# busanalizer.net
KiCad netlist of a schematic drawn in Altium Designer
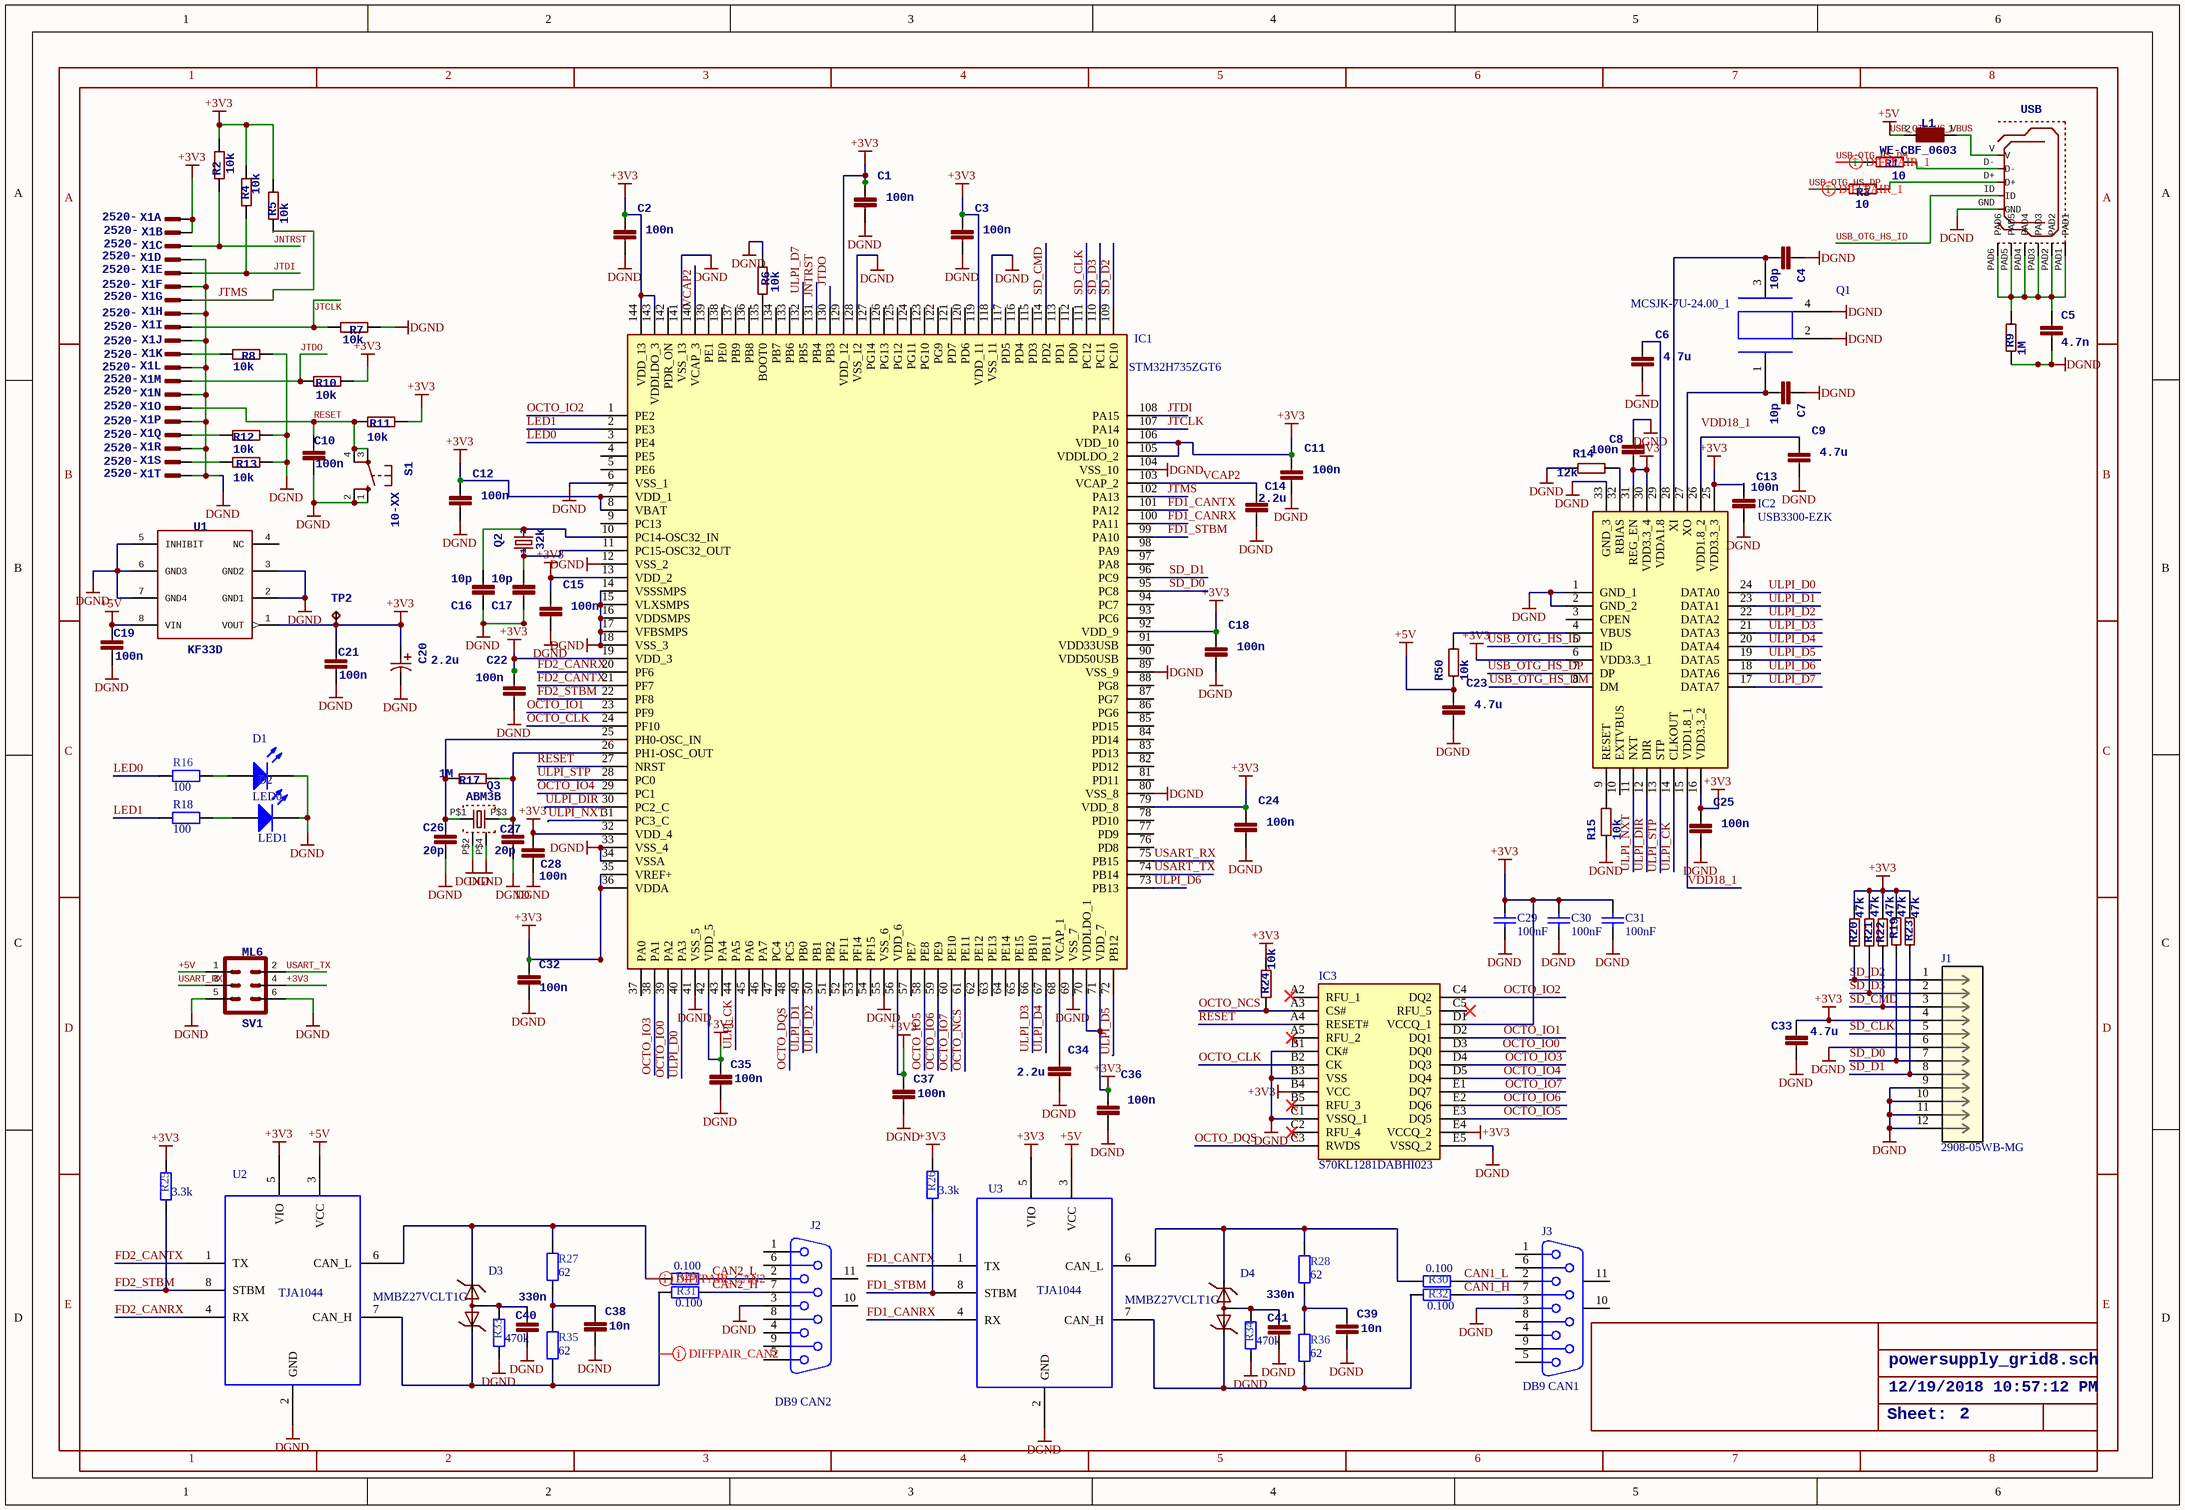
[diagram p0: busanalizer.SchDoc]

(export (version "E")
  (design (tool "Eeschema 10.0.6"))
  (components
    (comp (ref "C1")
      (value "100n")
      (footprint "C0402")
      (description "<B>CAPACITOR</B>, European symbol")
      (libsource (lib "rcl") (part "C-EUC0402"))
    )
    (comp (ref "C2")
      (value "100n")
      (footprint "C0402")
      (description "<B>CAPACITOR</B>, European symbol")
      (libsource (lib "rcl") (part "C-EUC0402"))
    )
    (comp (ref "C3")
      (value "100n")
      (footprint "C0402")
      (description "<B>CAPACITOR</B>, European symbol")
      (libsource (lib "rcl") (part "C-EUC0402"))
    )
    (comp (ref "C4")
      (value "10p")
      (footprint "C0402")
      (description "<B>CAPACITOR</B>, European symbol")
      (libsource (lib "") (part "C-EUC0402_2"))
    )
    (comp (ref "C5")
      (value "4.7n")
      (footprint "C0805")
      (description "<B>CAPACITOR</B>, European symbol")
      (libsource (lib "rcl") (part "C-EUC0805"))
    )
    (comp (ref "C6")
      (value "4.7u")
      (footprint "rcl:C0805")
      (description "<B>CAPACITOR</B>, European symbol")
      (libsource (lib "rcl") (part "C-EUC0402"))
    )
    (comp (ref "C7")
      (value "10p")
      (footprint "C0402")
      (description "<B>CAPACITOR</B>, European symbol")
      (libsource (lib "") (part "C-EUC0402_2"))
    )
    (comp (ref "C8")
      (value "100n")
      (footprint "C0402")
      (description "<B>CAPACITOR</B>, European symbol")
      (libsource (lib "") (part "C-EUC0402_1"))
    )
    (comp (ref "C9")
      (value "4.7u")
      (footprint "rcl:C0805")
      (description "<B>CAPACITOR</B>, European symbol")
      (libsource (lib "rcl") (part "C-EUC0402"))
    )
    (comp (ref "C10")
      (value "100n")
      (footprint "C0402")
      (description "<B>CAPACITOR</B>, European symbol")
      (libsource (lib "rcl") (part "C-EUC0402"))
    )
    (comp (ref "C11")
      (value "100n")
      (footprint "C0402")
      (description "<B>CAPACITOR</B>, European symbol")
      (libsource (lib "rcl") (part "C-EUC0402"))
    )
    (comp (ref "C12")
      (value "100n")
      (footprint "C0402")
      (description "<B>CAPACITOR</B>, European symbol")
      (libsource (lib "rcl") (part "C-EUC0402"))
    )
    (comp (ref "C13")
      (value "100n")
      (footprint "C0402")
      (description "<B>CAPACITOR</B>, European symbol")
      (libsource (lib "rcl") (part "C-EUC0402"))
    )
    (comp (ref "C14")
      (value "2.2u")
      (footprint "rcl:C0805")
      (description "<B>CAPACITOR</B>, European symbol")
      (libsource (lib "rcl") (part "C-EUC0402"))
    )
    (comp (ref "C15")
      (value "100n")
      (footprint "C0402")
      (description "<B>CAPACITOR</B>, European symbol")
      (libsource (lib "rcl") (part "C-EUC0402"))
    )
    (comp (ref "C16")
      (value "10p")
      (footprint "C0402")
      (description "<B>CAPACITOR</B>, European symbol")
      (libsource (lib "") (part "C-EUC0402_1"))
    )
    (comp (ref "C17")
      (value "10p")
      (footprint "C0402")
      (description "<B>CAPACITOR</B>, European symbol")
      (libsource (lib "") (part "C-EUC0402_1"))
    )
    (comp (ref "C18")
      (value "100n")
      (footprint "C0402")
      (description "<B>CAPACITOR</B>, European symbol")
      (libsource (lib "rcl") (part "C-EUC0402"))
    )
    (comp (ref "C19")
      (value "100n")
      (footprint "C0603")
      (description "<B>CAPACITOR</B>, European symbol")
      (libsource (lib "rcl") (part "C-EUC0603"))
    )
    (comp (ref "C20")
      (value "2.2u")
      (footprint "Panasonic-EEEFT_EEEH:CAPAE430X610N")
      (fields
        (field (name "MPN") "EEE-FT0J101AR")
        (field (name "TOLERANCE") "±20 %")
        (field (name "MPN_1") "EEE-FT1A680AR")
      )
      (libsource (lib "Panasonic-EEEFT_EEEH") (part "EEE--CASE-B"))
    )
    (comp (ref "C21")
      (value "100n")
      (footprint "C0603")
      (description "<B>CAPACITOR</B>, European symbol")
      (libsource (lib "rcl") (part "C-EUC0603"))
    )
    (comp (ref "C22")
      (value "100n")
      (footprint "C0402")
      (description "<B>CAPACITOR</B>, European symbol")
      (libsource (lib "rcl") (part "C-EUC0402"))
    )
    (comp (ref "C23")
      (value "4.7u")
      (footprint "rcl:C0805")
      (description "<B>CAPACITOR</B>, European symbol")
      (libsource (lib "rcl") (part "C-EUC0402"))
    )
    (comp (ref "C24")
      (value "100n")
      (footprint "C0402")
      (description "<B>CAPACITOR</B>, European symbol")
      (libsource (lib "rcl") (part "C-EUC0402"))
    )
    (comp (ref "C25")
      (value "100n")
      (footprint "C0402")
      (description "<B>CAPACITOR</B>, European symbol")
      (libsource (lib "rcl") (part "C-EUC0402"))
    )
    (comp (ref "C26")
      (value "20p")
      (footprint "C0402")
      (description "<B>CAPACITOR</B>, European symbol")
      (libsource (lib "rcl") (part "C-EUC0402"))
    )
    (comp (ref "C27")
      (value "20p")
      (footprint "C0402")
      (description "<B>CAPACITOR</B>, European symbol")
      (libsource (lib "rcl") (part "C-EUC0402"))
    )
    (comp (ref "C28")
      (value "100n")
      (footprint "C0402")
      (description "<B>CAPACITOR</B>, European symbol")
      (libsource (lib "rcl") (part "C-EUC0402"))
    )
    (comp (ref "C29")
      (value "100nF")
      (footprint "C0402")
      (description "Capacitor, MLCC, 100nF, 16V, X7R, 10%, 0402, T=0,5mm")
      (fields
        (field (name "INTERNAL_PART_NUMBER") "MCD-00102")
        (field (name "MANUFACTURER_PART_NUMBER") "CC0402KRX7R7BB104")
        (field (name "PROVIDED_BY") "SUBCO")
      )
      (libsource (lib "MCD_PARTS_database") (part "Capacitor"))
    )
    (comp (ref "C30")
      (value "100nF")
      (footprint "C0402")
      (description "Capacitor, MLCC, 100nF, 16V, X7R, 10%, 0402, T=0,5mm")
      (fields
        (field (name "INTERNAL_PART_NUMBER") "MCD-00102")
        (field (name "MANUFACTURER_PART_NUMBER") "CC0402KRX7R7BB104")
        (field (name "PROVIDED_BY") "SUBCO")
      )
      (libsource (lib "MCD_PARTS_database") (part "Capacitor"))
    )
    (comp (ref "C31")
      (value "100nF")
      (footprint "C0402")
      (description "Capacitor, MLCC, 100nF, 16V, X7R, 10%, 0402, T=0,5mm")
      (fields
        (field (name "INTERNAL_PART_NUMBER") "MCD-00102")
        (field (name "MANUFACTURER_PART_NUMBER") "CC0402KRX7R7BB104")
        (field (name "PROVIDED_BY") "SUBCO")
      )
      (libsource (lib "MCD_PARTS_database") (part "Capacitor"))
    )
    (comp (ref "C32")
      (value "100n")
      (footprint "C0402")
      (description "<B>CAPACITOR</B>, European symbol")
      (libsource (lib "rcl") (part "C-EUC0402"))
    )
    (comp (ref "C33")
      (value "4.7u")
      (footprint "rcl:C0805")
      (description "<B>CAPACITOR</B>, European symbol")
      (libsource (lib "rcl") (part "C-EUC0402"))
    )
    (comp (ref "C34")
      (value "2.2u")
      (footprint "rcl:C0805")
      (description "<B>CAPACITOR</B>, European symbol")
      (libsource (lib "rcl") (part "C-EUC0402"))
    )
    (comp (ref "C35")
      (value "100n")
      (footprint "C0402")
      (description "<B>CAPACITOR</B>, European symbol")
      (libsource (lib "rcl") (part "C-EUC0402"))
    )
    (comp (ref "C36")
      (value "100n")
      (footprint "C0402")
      (description "<B>CAPACITOR</B>, European symbol")
      (libsource (lib "rcl") (part "C-EUC0402"))
    )
    (comp (ref "C37")
      (value "100n")
      (footprint "C0402")
      (description "<B>CAPACITOR</B>, European symbol")
      (libsource (lib "rcl") (part "C-EUC0402"))
    )
    (comp (ref "C38")
      (value "10n")
      (footprint "C0805")
      (description "<B>CAPACITOR</B>, European symbol")
      (libsource (lib "rcl") (part "C-EUC0402"))
    )
    (comp (ref "C39")
      (value "10n")
      (footprint "C0805")
      (description "<B>CAPACITOR</B>, European symbol")
      (libsource (lib "rcl") (part "C-EUC0402"))
    )
    (comp (ref "C40")
      (value "330n")
      (footprint "C0805")
      (description "<B>CAPACITOR</B>, European symbol")
      (libsource (lib "rcl") (part "C-EUC0402"))
    )
    (comp (ref "C41")
      (value "330n")
      (footprint "C0805")
      (description "<B>CAPACITOR</B>, European symbol")
      (libsource (lib "rcl") (part "C-EUC0402"))
    )
    (comp (ref "D1")
      (value "LED0")
      (footprint "LED-0")
      (description "Typical INFRARED GaAs LED")
      (fields (field (name "PUBLISHER") "Altium Limited"))
      (libsource (lib "Miscellaneous Devices") (part "LED0"))
    )
    (comp (ref "D2")
      (value "LED1")
      (footprint "LED-0")
      (description "Typical INFRARED GaAs LED")
      (fields (field (name "PUBLISHER") "Altium Limited"))
      (libsource (lib "Miscellaneous Devices") (part "LED0"))
    )
    (comp (ref "D3")
      (value "MMBZ27VCLT1G")
      (footprint "SOT23")
      (libsource (lib "MMBZ27VCLT1G") (part "MMBZ27VCLT1G"))
    )
    (comp (ref "D4")
      (value "MMBZ27VCLT1G")
      (footprint "SOT23")
      (libsource (lib "MMBZ27VCLT1G") (part "MMBZ27VCLT1G"))
    )
    (comp (ref "IC1")
      (value "STM32H735ZGT6")
      (footprint "SamacSys:QFP50P2200X2200X160-144N")
      (description "Integrated Circuit")
      (libsource (lib "*") (part "STM32H735ZGT6"))
    )
    (comp (ref "IC2")
      (value "USB3300-EZK")
      (footprint "SamacSys:QFN50P500X500X100-33N-D")
      (description "Integrated Circuit")
      (fields (field (name "MOUSER2 PART NUMBER") "886-USB3300-EZK"))
      (libsource (lib "*") (part "USB3300-EZK"))
    )
    (comp (ref "IC3")
      (value "S70KL1281DABHI023")
      (footprint "SamacSys:BGA24C100P5X5_600X800X100")
      (description "Integrated Circuit")
      (libsource (lib "*") (part "S70KL1281DABHI023"))
    )
    (comp (ref "J1")
      (value "2908-05WB-MG")
      (footprint "CONN_3M_2900")
      (description "No Description Available")
      (fields (field (name "COPYRIGHT") "Copyright (C) 2018 Accelerated Designs. All rights reserved"))
      (libsource (lib "2021-01-25_15-19-21") (part "2908-05WB-MG"))
    )
    (comp (ref "J2")
      (value "DB9 CAN2")
      (footprint "DSUB1.385-2H9")
      (description "Receptacle Assembly, 9 Position, Right Angle")
      (fields (field (name "PUBLISHER") "Altium Limited"))
      (libsource (lib "Miscellaneous Connectors") (part "D Connector 9"))
    )
    (comp (ref "J3")
      (value "DB9 CAN1")
      (footprint "DSUB1.385-2H9")
      (description "Receptacle Assembly, 9 Position, Right Angle")
      (fields (field (name "PUBLISHER") "Altium Limited"))
      (libsource (lib "Miscellaneous Connectors") (part "D Connector 9"))
    )
    (comp (ref "L1")
      (value "WE-CBF_0603")
      (footprint "WE-CBF:0603")
      (fields (field (name "MPN") "742792695"))
      (libsource (lib "WE-CBF") (part "WE-CBF_0603"))
    )
    (comp (ref "Q1")
      (value "MCSJK-7U-24.00_1")
      (footprint "MCSJK-7U-24.00_1")
      (libsource (lib "MCSJK-7U-24.00") (part "MCSJK-7U-24.00_1"))
    )
    (comp (ref "Q2")
      (value "32k")
      (footprint "crystal:TC26V")
      (description "<b>CRYSTAL</b>")
      (fields (field (name "1") "1") (field (name "2") "2"))
      (libsource (lib "crystal") (part "CRYSTALTC26V"))
    )
    (comp (ref "Q3")
      (value "ABM3B")
      (footprint "crystal_my:ABM3B")
      (libsource (lib "crystal_my") (part "ABM3B"))
    )
    (comp (ref "R1")
      (value "10")
      (footprint "R0805")
      (description "<B>RESISTOR</B>, European symbol")
      (libsource (lib "rcl") (part "R-EU_R0805"))
    )
    (comp (ref "R2")
      (value "10k")
      (footprint "R0805")
      (description "<B>RESISTOR</B>, European symbol")
      (libsource (lib "rcl") (part "R-EU_R0805"))
    )
    (comp (ref "R3")
      (value "10")
      (footprint "R0805")
      (description "<B>RESISTOR</B>, European symbol")
      (libsource (lib "rcl") (part "R-EU_R0805"))
    )
    (comp (ref "R4")
      (value "10k")
      (footprint "R0805")
      (description "<B>RESISTOR</B>, European symbol")
      (libsource (lib "rcl") (part "R-EU_R0805"))
    )
    (comp (ref "R5")
      (value "10k")
      (footprint "R0805")
      (description "<B>RESISTOR</B>, European symbol")
      (libsource (lib "rcl") (part "R-EU_R0805"))
    )
    (comp (ref "R6")
      (value "10k")
      (footprint "R0805")
      (description "<B>RESISTOR</B>, European symbol")
      (libsource (lib "rcl") (part "R-EU_R0805"))
    )
    (comp (ref "R7")
      (value "10k")
      (footprint "R0805")
      (description "<B>RESISTOR</B>, European symbol")
      (libsource (lib "rcl") (part "R-EU_R0805"))
    )
    (comp (ref "R8")
      (value "10k")
      (footprint "R0805")
      (description "<B>RESISTOR</B>, European symbol")
      (libsource (lib "rcl") (part "R-EU_R0805"))
    )
    (comp (ref "R9")
      (value "1M")
      (footprint "R0805")
      (description "<B>RESISTOR</B>, European symbol")
      (libsource (lib "rcl") (part "R-EU_R0805"))
    )
    (comp (ref "R10")
      (value "10k")
      (footprint "R0805")
      (description "<B>RESISTOR</B>, European symbol")
      (libsource (lib "rcl") (part "R-EU_R0805"))
    )
    (comp (ref "R11")
      (value "10k")
      (footprint "R0805")
      (description "<B>RESISTOR</B>, European symbol")
      (libsource (lib "rcl") (part "R-EU_R0805"))
    )
    (comp (ref "R12")
      (value "10k")
      (footprint "R0805")
      (description "<B>RESISTOR</B>, European symbol")
      (libsource (lib "rcl") (part "R-EU_R0805"))
    )
    (comp (ref "R13")
      (value "10k")
      (footprint "R0805")
      (description "<B>RESISTOR</B>, European symbol")
      (libsource (lib "rcl") (part "R-EU_R0805"))
    )
    (comp (ref "R14") (value "12k") (footprint "R0805") (libsource (lib "rcl") (part "R-EU_R0805")))
    (comp (ref "R15") (value "10k") (footprint "R0805") (libsource (lib "rcl") (part "R-EU_R0805")))
    (comp (ref "R16")
      (value "100")
      (footprint "6-0805_L")
      (description "Resistor")
      (fields (field (name "Comment") "Res2") (field (name "PUBLISHER") "Altium Limited"))
      (libsource (lib "Miscellaneous Devices") (part "Res2"))
    )
    (comp (ref "R17")
      (value "1M")
      (footprint "R0402")
      (description "<B>RESISTOR</B>, European symbol")
      (libsource (lib "rcl") (part "R-EU_R0402"))
    )
    (comp (ref "R18")
      (value "100")
      (footprint "6-0805_L")
      (description "Resistor")
      (fields (field (name "Comment") "Res2") (field (name "PUBLISHER") "Altium Limited"))
      (libsource (lib "Miscellaneous Devices") (part "Res2"))
    )
    (comp (ref "R19")
      (value "47k")
      (footprint "R0805")
      (description "<B>RESISTOR</B>, European symbol")
      (libsource (lib "rcl") (part "R-EU_R0805"))
    )
    (comp (ref "R20")
      (value "47k")
      (footprint "R0805")
      (description "<B>RESISTOR</B>, European symbol")
      (libsource (lib "rcl") (part "R-EU_R0805"))
    )
    (comp (ref "R21")
      (value "47k")
      (footprint "R0805")
      (description "<B>RESISTOR</B>, European symbol")
      (libsource (lib "rcl") (part "R-EU_R0805"))
    )
    (comp (ref "R22")
      (value "47k")
      (footprint "R0805")
      (description "<B>RESISTOR</B>, European symbol")
      (libsource (lib "rcl") (part "R-EU_R0805"))
    )
    (comp (ref "R23")
      (value "47k")
      (footprint "R0805")
      (description "<B>RESISTOR</B>, European symbol")
      (libsource (lib "rcl") (part "R-EU_R0805"))
    )
    (comp (ref "R24")
      (value "10k")
      (footprint "R0805")
      (description "<B>RESISTOR</B>, European symbol")
      (libsource (lib "rcl") (part "R-EU_R0805"))
    )
    (comp (ref "R25")
      (value "3.3k")
      (footprint "R0805")
      (description "Resistor")
      (fields (field (name "Comment") "Res2") (field (name "PUBLISHER") "Altium Limited"))
      (libsource (lib "") (part "Res2_1"))
    )
    (comp (ref "R26")
      (value "3.3k")
      (footprint "R0805")
      (description "Resistor")
      (fields (field (name "Comment") "Res2") (field (name "PUBLISHER") "Altium Limited"))
      (libsource (lib "") (part "Res2_1"))
    )
    (comp (ref "R27")
      (value "62")
      (footprint "R0805")
      (description "Resistor")
      (fields (field (name "Comment") "Res2") (field (name "PUBLISHER") "Altium Limited"))
      (libsource (lib "") (part "Res2_1"))
    )
    (comp (ref "R28")
      (value "62")
      (footprint "R0805")
      (description "Resistor")
      (fields (field (name "Comment") "Res2") (field (name "PUBLISHER") "Altium Limited"))
      (libsource (lib "") (part "Res2_1"))
    )
    (comp (ref "R29")
      (value "0.100")
      (footprint "R0805")
      (description "Resistor")
      (fields (field (name "Comment") "Res2") (field (name "PUBLISHER") "Altium Limited"))
      (libsource (lib "Miscellaneous Devices") (part "Res2"))
    )
    (comp (ref "R30")
      (value "0.100")
      (footprint "R0805")
      (description "Resistor")
      (fields (field (name "Comment") "Res2") (field (name "PUBLISHER") "Altium Limited"))
      (libsource (lib "Miscellaneous Devices") (part "Res2"))
    )
    (comp (ref "R31")
      (value "0.100")
      (footprint "R0805")
      (description "Resistor")
      (fields (field (name "Comment") "Res2") (field (name "PUBLISHER") "Altium Limited"))
      (libsource (lib "Miscellaneous Devices") (part "Res2"))
    )
    (comp (ref "R32")
      (value "0.100")
      (footprint "R0805")
      (description "Resistor")
      (fields (field (name "Comment") "Res2") (field (name "PUBLISHER") "Altium Limited"))
      (libsource (lib "Miscellaneous Devices") (part "Res2"))
    )
    (comp (ref "R33")
      (value "470k")
      (footprint "R0805")
      (description "Resistor")
      (fields (field (name "Comment") "Res2") (field (name "PUBLISHER") "Altium Limited"))
      (libsource (lib "") (part "Res2_1"))
    )
    (comp (ref "R34")
      (value "470k")
      (footprint "R0805")
      (description "Resistor")
      (fields (field (name "Comment") "Res2") (field (name "PUBLISHER") "Altium Limited"))
      (libsource (lib "") (part "Res2_1"))
    )
    (comp (ref "R35")
      (value "62")
      (footprint "R0805")
      (description "Resistor")
      (fields (field (name "Comment") "Res2") (field (name "PUBLISHER") "Altium Limited"))
      (libsource (lib "") (part "Res2_1"))
    )
    (comp (ref "R36")
      (value "62")
      (footprint "R0805")
      (description "Resistor")
      (fields (field (name "Comment") "Res2") (field (name "PUBLISHER") "Altium Limited"))
      (libsource (lib "") (part "Res2_1"))
    )
    (comp (ref "R50") (value "10k") (footprint "R0805") (libsource (lib "rcl") (part "R-EU_R0805")))
    (comp (ref "S1")
      (value "10-XX")
      (footprint "switch-omron:B3F-10XX")
      (description "<b>OMRON SWITCH</b>")
      (fields (field (name "MPN") "B3F-1000"))
      (libsource (lib "switch-omron") (part "10-XX"))
    )
    (comp (ref "SV1")
      (value "ML6")
      (footprint "con-harting-ml:ML6")
      (description "<b>HARTING</b>")
      (libsource (lib "con-harting-ml") (part "ML6"))
    )
    (comp (ref "TP2")
      (value "TPB2,54")
      (footprint "B2,54")
      (description "<b>Test pad</b>")
      (libsource (lib "testpad") (part "TPB2,54"))
    )
    (comp (ref "U1") (value "KF33D") (footprint "KF33BD:SO8") (libsource (lib "KF33BD") (part "KF33D")))
    (comp (ref "U2") (value "TJA1044") (footprint "SO8") (libsource (lib "TJA1044") (part "TJA1044")))
    (comp (ref "U3") (value "TJA1044") (footprint "SO8") (libsource (lib "TJA1044") (part "TJA1044")))
    (comp (ref "USB1")
      (value "USB_MICROB")
      (footprint "usb_hinrose:USB_MICROB_PACKAGE")
      (description "This is the hirose ZX62-B-5PA(11) MICRO-USB B Type female connection.")
      (fields (field (name "USB") "USB"))
      (libsource (lib "usb_hinrose") (part "USB_MICROB"))
    )
    (comp (ref "X1")
      (value "2520-")
      (footprint "con-3m:PAK100/2500-20")
      (description "<b>3M (TM) Pak 100 4-Wall Header</b><p>\nSource: 3M")
      (libsource (lib "con-3m") (part "2520-"))
    )
  )
  (nets
    (net (code "1") (name "+3V3") (class "Default")
      (node (ref "C1") (pin "1") (pinfunction "1_1") (pintype "passive"))
      (node (ref "C11") (pin "1") (pinfunction "1_1") (pintype "passive"))
      (node (ref "C12") (pin "1") (pinfunction "1_1") (pintype "passive"))
      (node (ref "C13") (pin "1") (pinfunction "1_1") (pintype "passive"))
      (node (ref "C15") (pin "1") (pinfunction "1_1") (pintype "passive"))
      (node (ref "C18") (pin "1") (pinfunction "1_1") (pintype "passive"))
      (node (ref "C2") (pin "1") (pinfunction "1_1") (pintype "passive"))
      (node (ref "C20") (pin "1") (pinfunction "1_1") (pintype "passive"))
      (node (ref "C21") (pin "1") (pinfunction "1_1") (pintype "passive"))
      (node (ref "C22") (pin "1") (pinfunction "1_1") (pintype "passive"))
      (node (ref "C24") (pin "1") (pinfunction "1_1") (pintype "passive"))
      (node (ref "C25") (pin "1") (pinfunction "1_1") (pintype "passive"))
      (node (ref "C28") (pin "1") (pinfunction "1_1") (pintype "passive"))
      (node (ref "C29") (pin "2") (pinfunction "2_2") (pintype "passive"))
      (node (ref "C3") (pin "1") (pinfunction "1_1") (pintype "passive"))
      (node (ref "C30") (pin "2") (pinfunction "2_2") (pintype "passive"))
      (node (ref "C31") (pin "2") (pinfunction "2_2") (pintype "passive"))
      (node (ref "C32") (pin "1") (pinfunction "1_1") (pintype "passive"))
      (node (ref "C33") (pin "1") (pinfunction "1_1") (pintype "passive"))
      (node (ref "C35") (pin "1") (pinfunction "1_1") (pintype "passive"))
      (node (ref "C36") (pin "1") (pinfunction "1_1") (pintype "passive"))
      (node (ref "C37") (pin "1") (pinfunction "1_1") (pintype "passive"))
      (node (ref "C8") (pin "1") (pinfunction "1_1") (pintype "passive"))
      (node (ref "IC1") (pin "105") (pinfunction "VDDLDO_2_105") (pintype "passive"))
      (node (ref "IC1") (pin "106") (pinfunction "VDD_10_106") (pintype "passive"))
      (node (ref "IC1") (pin "119") (pinfunction "VDD_11_119") (pintype "passive"))
      (node (ref "IC1") (pin "129") (pinfunction "VDD_12_129") (pintype "passive"))
      (node (ref "IC1") (pin "13") (pinfunction "VDD_2_13") (pintype "passive"))
      (node (ref "IC1") (pin "143") (pinfunction "VDDLDO_3_143") (pintype "passive"))
      (node (ref "IC1") (pin "144") (pinfunction "VDD_13_144") (pintype "passive"))
      (node (ref "IC1") (pin "19") (pinfunction "VDD_3_19") (pintype "passive"))
      (node (ref "IC1") (pin "32") (pinfunction "VDD_4_32") (pintype "passive"))
      (node (ref "IC1") (pin "35") (pinfunction "VREF+_35") (pintype "passive"))
      (node (ref "IC1") (pin "36") (pinfunction "VDDA_36") (pintype "passive"))
      (node (ref "IC1") (pin "42") (pinfunction "VDD_5_42") (pintype "passive"))
      (node (ref "IC1") (pin "56") (pinfunction "VDD_6_56") (pintype "passive"))
      (node (ref "IC1") (pin "7") (pinfunction "VDD_1_7") (pintype "passive"))
      (node (ref "IC1") (pin "70") (pinfunction "VDDLDO_1_70") (pintype "passive"))
      (node (ref "IC1") (pin "71") (pinfunction "VDD_7_71") (pintype "passive"))
      (node (ref "IC1") (pin "79") (pinfunction "VDD_8_79") (pintype "passive"))
      (node (ref "IC1") (pin "8") (pinfunction "VBAT_8") (pintype "passive"))
      (node (ref "IC1") (pin "92") (pinfunction "VDD_9_92") (pintype "passive"))
      (node (ref "IC2") (pin "16") (pinfunction "VDD3.3_2_16") (pintype "passive"))
      (node (ref "IC2") (pin "25") (pinfunction "VDD3.3_3_25") (pintype "passive"))
      (node (ref "IC2") (pin "30") (pinfunction "VDD3.3_4_30") (pintype "passive"))
      (node (ref "IC2") (pin "31") (pinfunction "REG_EN_31") (pintype "passive"))
      (node (ref "IC2") (pin "6") (pinfunction "VDD3.3_1_6") (pintype "passive"))
      (node (ref "IC3") (pin "B4") (pinfunction "VCC_B4") (pintype "passive"))
      (node (ref "IC3") (pin "D1") (pinfunction "VCCQ_1_D1") (pintype "passive"))
      (node (ref "IC3") (pin "E4") (pinfunction "VCCQ_2_E4") (pintype "passive"))
      (node (ref "J1") (pin "4") (pinfunction "4_4") (pintype "passive"))
      (node (ref "R10") (pin "1") (pinfunction "1_1") (pintype "passive"))
      (node (ref "R11") (pin "1") (pinfunction "1_1") (pintype "passive"))
      (node (ref "R19") (pin "2") (pinfunction "2_2") (pintype "passive"))
      (node (ref "R2") (pin "2") (pinfunction "2_2") (pintype "passive"))
      (node (ref "R20") (pin "2") (pinfunction "2_2") (pintype "passive"))
      (node (ref "R21") (pin "2") (pinfunction "2_2") (pintype "passive"))
      (node (ref "R22") (pin "2") (pinfunction "2_2") (pintype "passive"))
      (node (ref "R23") (pin "2") (pinfunction "2_2") (pintype "passive"))
      (node (ref "R24") (pin "2") (pinfunction "2_2") (pintype "passive"))
      (node (ref "R25") (pin "2") (pinfunction "2_2") (pintype "passive"))
      (node (ref "R26") (pin "2") (pinfunction "2_2") (pintype "passive"))
      (node (ref "R4") (pin "2") (pinfunction "2_2") (pintype "passive"))
      (node (ref "R5") (pin "2") (pinfunction "2_2") (pintype "passive"))
      (node (ref "SV1") (pin "4") (pinfunction "4_4") (pintype "passive"))
      (node (ref "TP2") (pin "TP") (pinfunction "TP_TP") (pintype "passive"))
      (node (ref "U1") (pin "1") (pinfunction "VOUT_1") (pintype "output"))
      (node (ref "U2") (pin "5") (pinfunction "VIO_5") (pintype "passive"))
      (node (ref "U3") (pin "5") (pinfunction "VIO_5") (pintype "passive"))
      (node (ref "X1") (pin "1") (pinfunction "KL_1") (pintype "passive"))
      (node (ref "X1") (pin "2") (pinfunction "KL_2") (pintype "passive"))
    )
    (net (code "2") (name "+5V") (class "Default")
      (node (ref "C19") (pin "1") (pinfunction "1_1") (pintype "passive"))
      (node (ref "C23") (pin "1") (pinfunction "1_1") (pintype "passive"))
      (node (ref "L1") (pin "2") (pinfunction "2_2") (pintype "passive"))
      (node (ref "R50") (pin "1") (pinfunction "1_1") (pintype "passive"))
      (node (ref "SV1") (pin "1") (pinfunction "1_1") (pintype "passive"))
      (node (ref "U1") (pin "8") (pinfunction "VIN_8") (pintype "passive"))
      (node (ref "U2") (pin "3") (pinfunction "VCC_3") (pintype "passive"))
      (node (ref "U3") (pin "3") (pinfunction "VCC_3") (pintype "passive"))
    )
    (net (code "3") (name "/CAN1_H") (class "Default")
      (node (ref "J3") (pin "7") (pinfunction "7_7") (pintype "passive"))
      (node (ref "R32") (pin "2") (pinfunction "2_2") (pintype "passive"))
    )
    (net (code "4") (name "/CAN1_L") (class "Default")
      (node (ref "J3") (pin "2") (pinfunction "2_2") (pintype "passive"))
      (node (ref "R30") (pin "2") (pinfunction "2_2") (pintype "passive"))
    )
    (net (code "5") (name "/CAN2_H") (class "Default")
      (node (ref "J2") (pin "7") (pinfunction "7_7") (pintype "passive"))
      (node (ref "R31") (pin "2") (pinfunction "2_2") (pintype "passive"))
    )
    (net (code "6") (name "/CAN2_L") (class "Default")
      (node (ref "J2") (pin "2") (pinfunction "2_2") (pintype "passive"))
      (node (ref "R29") (pin "2") (pinfunction "2_2") (pintype "passive"))
    )
    (net (code "7") (name "/FD1_CANRX") (class "Default")
      (node (ref "IC1") (pin "100") (pinfunction "PA11_100") (pintype "passive"))
      (node (ref "U3") (pin "4") (pinfunction "RX_4") (pintype "passive"))
    )
    (net (code "8") (name "/FD1_CANTX") (class "Default")
      (node (ref "IC1") (pin "101") (pinfunction "PA12_101") (pintype "passive"))
      (node (ref "U3") (pin "1") (pinfunction "TX_1") (pintype "passive"))
    )
    (net (code "9") (name "/FD1_STBM") (class "Default")
      (node (ref "IC1") (pin "99") (pinfunction "PA10_99") (pintype "passive"))
      (node (ref "R26") (pin "1") (pinfunction "1_1") (pintype "passive"))
      (node (ref "U3") (pin "8") (pinfunction "STBM_8") (pintype "passive"))
    )
    (net (code "10") (name "/FD2_CANRX") (class "Default")
      (node (ref "IC1") (pin "20") (pinfunction "PF6_20") (pintype "passive"))
      (node (ref "U2") (pin "4") (pinfunction "RX_4") (pintype "passive"))
    )
    (net (code "11") (name "/FD2_CANTX") (class "Default")
      (node (ref "IC1") (pin "21") (pinfunction "PF7_21") (pintype "passive"))
      (node (ref "U2") (pin "1") (pinfunction "TX_1") (pintype "passive"))
    )
    (net (code "12") (name "/FD2_STBM") (class "Default")
      (node (ref "IC1") (pin "22") (pinfunction "PF8_22") (pintype "passive"))
      (node (ref "R25") (pin "1") (pinfunction "1_1") (pintype "passive"))
      (node (ref "U2") (pin "8") (pinfunction "STBM_8") (pintype "passive"))
    )
    (net (code "13") (name "/JNTRST") (class "Default")
      (node (ref "IC1") (pin "131") (pinfunction "PB4_131") (pintype "passive"))
      (node (ref "R2") (pin "1") (pinfunction "1_1") (pintype "passive"))
      (node (ref "X1") (pin "3") (pinfunction "KL_3") (pintype "passive"))
    )
    (net (code "14") (name "/JTCLK") (class "Default")
      (node (ref "IC1") (pin "107") (pinfunction "PA14_107") (pintype "passive"))
      (node (ref "R7") (pin "2") (pinfunction "2_2") (pintype "passive"))
      (node (ref "X1") (pin "9") (pinfunction "KL_9") (pintype "passive"))
    )
    (net (code "15") (name "/JTDI") (class "Default")
      (node (ref "IC1") (pin "108") (pinfunction "PA15_108") (pintype "passive"))
      (node (ref "R4") (pin "1") (pinfunction "1_1") (pintype "passive"))
      (node (ref "X1") (pin "5") (pinfunction "KL_5") (pintype "passive"))
    )
    (net (code "16") (name "/JTDO") (class "Default")
      (node (ref "IC1") (pin "130") (pinfunction "PB3_130") (pintype "passive"))
      (node (ref "R10") (pin "2") (pinfunction "2_2") (pintype "passive"))
      (node (ref "X1") (pin "13") (pinfunction "KL_13") (pintype "passive"))
    )
    (net (code "17") (name "/JTMS") (class "Default")
      (node (ref "IC1") (pin "102") (pinfunction "PA13_102") (pintype "passive"))
      (node (ref "R5") (pin "1") (pinfunction "1_1") (pintype "passive"))
      (node (ref "X1") (pin "7") (pinfunction "KL_7") (pintype "passive"))
    )
    (net (code "18") (name "/LED0") (class "Default")
      (node (ref "IC1") (pin "3") (pinfunction "PE4_3") (pintype "passive"))
      (node (ref "R16") (pin "1") (pinfunction "1_1") (pintype "passive"))
    )
    (net (code "19") (name "/LED1") (class "Default")
      (node (ref "IC1") (pin "2") (pinfunction "PE3_2") (pintype "passive"))
      (node (ref "R18") (pin "1") (pinfunction "1_1") (pintype "passive"))
    )
    (net (code "20") (name "/OCTO_CLK") (class "Default")
      (node (ref "IC1") (pin "24") (pinfunction "PF10_24") (pintype "passive"))
      (node (ref "IC3") (pin "B2") (pinfunction "CK_B2") (pintype "passive"))
    )
    (net (code "21") (name "/OCTO_DQS") (class "Default")
      (node (ref "IC1") (pin "48") (pinfunction "PC5_48") (pintype "passive"))
      (node (ref "IC3") (pin "C3") (pinfunction "RWDS_C3") (pintype "passive"))
    )
    (net (code "22") (name "/OCTO_IO0") (class "Default")
      (node (ref "IC1") (pin "39") (pinfunction "PA2_39") (pintype "passive"))
      (node (ref "IC3") (pin "D3") (pinfunction "DQ0_D3") (pintype "passive"))
    )
    (net (code "23") (name "/OCTO_IO1") (class "Default")
      (node (ref "IC1") (pin "23") (pinfunction "PF9_23") (pintype "passive"))
      (node (ref "IC3") (pin "D2") (pinfunction "DQ1_D2") (pintype "passive"))
    )
    (net (code "24") (name "/OCTO_IO2") (class "Default")
      (node (ref "IC1") (pin "1") (pinfunction "PE2_1") (pintype "passive"))
      (node (ref "IC3") (pin "C4") (pinfunction "DQ2_C4") (pintype "passive"))
    )
    (net (code "25") (name "/OCTO_IO3") (class "Default")
      (node (ref "IC1") (pin "38") (pinfunction "PA1_38") (pintype "passive"))
      (node (ref "IC3") (pin "D4") (pinfunction "DQ3_D4") (pintype "passive"))
    )
    (net (code "26") (name "/OCTO_IO4") (class "Default")
      (node (ref "IC1") (pin "29") (pinfunction "PC1_29") (pintype "passive"))
      (node (ref "IC3") (pin "D5") (pinfunction "DQ4_D5") (pintype "passive"))
    )
    (net (code "27") (name "/OCTO_IO5") (class "Default")
      (node (ref "IC1") (pin "58") (pinfunction "PE8_58") (pintype "passive"))
      (node (ref "IC3") (pin "E3") (pinfunction "DQ5_E3") (pintype "passive"))
    )
    (net (code "28") (name "/OCTO_IO6") (class "Default")
      (node (ref "IC1") (pin "59") (pinfunction "PE9_59") (pintype "passive"))
      (node (ref "IC3") (pin "E2") (pinfunction "DQ6_E2") (pintype "passive"))
    )
    (net (code "29") (name "/OCTO_IO7") (class "Default")
      (node (ref "IC1") (pin "60") (pinfunction "PE10_60") (pintype "passive"))
      (node (ref "IC3") (pin "E1") (pinfunction "DQ7_E1") (pintype "passive"))
    )
    (net (code "30") (name "/OCTO_NCS") (class "Default")
      (node (ref "IC1") (pin "61") (pinfunction "PE11_61") (pintype "passive"))
      (node (ref "IC3") (pin "A3") (pinfunction "CS#_A3") (pintype "passive"))
      (node (ref "R24") (pin "1") (pinfunction "1_1") (pintype "passive"))
    )
    (net (code "31") (name "/RESET") (class "Default")
      (node (ref "C10") (pin "1") (pinfunction "1_1") (pintype "passive"))
      (node (ref "IC1") (pin "27") (pinfunction "NRST_27") (pintype "passive"))
      (node (ref "IC3") (pin "A4") (pinfunction "RESET#_A4") (pintype "passive"))
      (node (ref "R11") (pin "2") (pinfunction "2_2") (pintype "passive"))
      (node (ref "S1") (pin "3") (pinfunction "P_3") (pintype "passive"))
      (node (ref "S1") (pin "4") (pinfunction "P1_4") (pintype "passive"))
      (node (ref "X1") (pin "15") (pinfunction "KL_15") (pintype "passive"))
    )
    (net (code "32") (name "/SD_CLK") (class "Default")
      (node (ref "IC1") (pin "111") (pinfunction "PC12_111") (pintype "passive"))
      (node (ref "J1") (pin "5") (pinfunction "5_5") (pintype "passive"))
    )
    (net (code "33") (name "/SD_CMD") (class "Default")
      (node (ref "IC1") (pin "114") (pinfunction "PD2_114") (pintype "passive"))
      (node (ref "J1") (pin "3") (pinfunction "3_3") (pintype "passive"))
      (node (ref "R22") (pin "1") (pinfunction "1_1") (pintype "passive"))
    )
    (net (code "34") (name "/SD_D0") (class "Default")
      (node (ref "IC1") (pin "95") (pinfunction "PC8_95") (pintype "passive"))
      (node (ref "J1") (pin "7") (pinfunction "7_7") (pintype "passive"))
      (node (ref "R19") (pin "1") (pinfunction "1_1") (pintype "passive"))
    )
    (net (code "35") (name "/SD_D1") (class "Default")
      (node (ref "IC1") (pin "96") (pinfunction "PC9_96") (pintype "passive"))
      (node (ref "J1") (pin "8") (pinfunction "8_8") (pintype "passive"))
      (node (ref "R23") (pin "1") (pinfunction "1_1") (pintype "passive"))
    )
    (net (code "36") (name "/SD_D2") (class "Default")
      (node (ref "IC1") (pin "109") (pinfunction "PC10_109") (pintype "passive"))
      (node (ref "J1") (pin "1") (pinfunction "1_1") (pintype "passive"))
      (node (ref "R20") (pin "1") (pinfunction "1_1") (pintype "passive"))
    )
    (net (code "37") (name "/SD_D3") (class "Default")
      (node (ref "IC1") (pin "110") (pinfunction "PC11_110") (pintype "passive"))
      (node (ref "J1") (pin "2") (pinfunction "2_2") (pintype "passive"))
      (node (ref "R21") (pin "1") (pinfunction "1_1") (pintype "passive"))
    )
    (net (code "38") (name "/ULPI_CK") (class "Default")
      (node (ref "IC1") (pin "44") (pinfunction "PA5_44") (pintype "passive"))
      (node (ref "IC2") (pin "14") (pinfunction "CLKOUT_14") (pintype "passive"))
    )
    (net (code "39") (name "/ULPI_D0") (class "Default")
      (node (ref "IC1") (pin "40") (pinfunction "PA3_40") (pintype "passive"))
      (node (ref "IC2") (pin "24") (pinfunction "DATA0_24") (pintype "passive"))
    )
    (net (code "40") (name "/ULPI_D1") (class "Default")
      (node (ref "IC1") (pin "49") (pinfunction "PB0_49") (pintype "passive"))
      (node (ref "IC2") (pin "23") (pinfunction "DATA1_23") (pintype "passive"))
    )
    (net (code "41") (name "/ULPI_D2") (class "Default")
      (node (ref "IC1") (pin "50") (pinfunction "PB1_50") (pintype "passive"))
      (node (ref "IC2") (pin "22") (pinfunction "DATA2_22") (pintype "passive"))
    )
    (net (code "42") (name "/ULPI_D3") (class "Default")
      (node (ref "IC1") (pin "66") (pinfunction "PB10_66") (pintype "passive"))
      (node (ref "IC2") (pin "21") (pinfunction "DATA3_21") (pintype "passive"))
    )
    (net (code "43") (name "/ULPI_D4") (class "Default")
      (node (ref "IC1") (pin "67") (pinfunction "PB11_67") (pintype "passive"))
      (node (ref "IC2") (pin "20") (pinfunction "DATA4_20") (pintype "passive"))
    )
    (net (code "44") (name "/ULPI_D5") (class "Default")
      (node (ref "IC1") (pin "72") (pinfunction "PB12_72") (pintype "passive"))
      (node (ref "IC2") (pin "19") (pinfunction "DATA5_19") (pintype "passive"))
    )
    (net (code "45") (name "/ULPI_D6") (class "Default")
      (node (ref "IC1") (pin "73") (pinfunction "PB13_73") (pintype "passive"))
      (node (ref "IC2") (pin "18") (pinfunction "DATA6_18") (pintype "passive"))
    )
    (net (code "46") (name "/ULPI_D7") (class "Default")
      (node (ref "IC1") (pin "132") (pinfunction "PB5_132") (pintype "passive"))
      (node (ref "IC2") (pin "17") (pinfunction "DATA7_17") (pintype "passive"))
    )
    (net (code "47") (name "/ULPI_DIR") (class "Default")
      (node (ref "IC1") (pin "30") (pinfunction "PC2_C_30") (pintype "passive"))
      (node (ref "IC2") (pin "12") (pinfunction "DIR_12") (pintype "passive"))
    )
    (net (code "48") (name "/ULPI_NXT") (class "Default")
      (node (ref "IC1") (pin "31") (pinfunction "PC3_C_31") (pintype "passive"))
      (node (ref "IC2") (pin "11") (pinfunction "NXT_11") (pintype "passive"))
    )
    (net (code "49") (name "/ULPI_STP") (class "Default")
      (node (ref "IC1") (pin "28") (pinfunction "PC0_28") (pintype "passive"))
      (node (ref "IC2") (pin "13") (pinfunction "STP_13") (pintype "passive"))
    )
    (net (code "50") (name "/USART_RX") (class "Default")
      (node (ref "IC1") (pin "75") (pinfunction "PB15_75") (pintype "passive"))
      (node (ref "SV1") (pin "3") (pinfunction "3_3") (pintype "passive"))
    )
    (net (code "51") (name "/USART_TX") (class "Default")
      (node (ref "IC1") (pin "74") (pinfunction "PB14_74") (pintype "passive"))
      (node (ref "SV1") (pin "2") (pinfunction "2_2") (pintype "passive"))
    )
    (net (code "52") (name "/USB_OTG_HS_DM") (class "Default")
      (node (ref "IC2") (pin "8") (pinfunction "DM_8") (pintype "passive"))
      (node (ref "R1") (pin "2") (pinfunction "2_2") (pintype "passive"))
    )
    (net (code "53") (name "/USB_OTG_HS_DP") (class "Default")
      (node (ref "IC2") (pin "7") (pinfunction "DP_7") (pintype "passive"))
      (node (ref "R3") (pin "2") (pinfunction "2_2") (pintype "passive"))
    )
    (net (code "54") (name "/USB_OTG_HS_ID") (class "Default")
      (node (ref "IC2") (pin "5") (pinfunction "ID_5") (pintype "passive"))
      (node (ref "USB1") (pin "ID") (pinfunction "ID_ID") (pintype "passive"))
    )
    (net (code "55") (name "/VCAP2") (class "Default")
      (node (ref "C14") (pin "1") (pinfunction "1_1") (pintype "passive"))
      (node (ref "IC1") (pin "103") (pinfunction "VCAP_2_103") (pintype "passive"))
      (node (ref "IC1") (pin "140") (pinfunction "VCAP_3_140") (pintype "passive"))
    )
    (net (code "56") (name "/VDD18_1") (class "Default")
      (node (ref "IC2") (pin "15") (pinfunction "VDD1.8_1_15") (pintype "passive"))
    )
    (net (code "57") (name "DGND") (class "Default")
      (node (ref "C1") (pin "2") (pinfunction "2_2") (pintype "passive"))
      (node (ref "C10") (pin "2") (pinfunction "2_2") (pintype "passive"))
      (node (ref "C11") (pin "2") (pinfunction "2_2") (pintype "passive"))
      (node (ref "C12") (pin "2") (pinfunction "2_2") (pintype "passive"))
      (node (ref "C13") (pin "2") (pinfunction "2_2") (pintype "passive"))
      (node (ref "C14") (pin "2") (pinfunction "2_2") (pintype "passive"))
      (node (ref "C15") (pin "2") (pinfunction "2_2") (pintype "passive"))
      (node (ref "C16") (pin "1") (pinfunction "1_1") (pintype "passive"))
      (node (ref "C17") (pin "1") (pinfunction "1_1") (pintype "passive"))
      (node (ref "C18") (pin "2") (pinfunction "2_2") (pintype "passive"))
      (node (ref "C19") (pin "2") (pinfunction "2_2") (pintype "passive"))
      (node (ref "C2") (pin "2") (pinfunction "2_2") (pintype "passive"))
      (node (ref "C20") (pin "2") (pinfunction "2_2") (pintype "passive"))
      (node (ref "C21") (pin "2") (pinfunction "2_2") (pintype "passive"))
      (node (ref "C22") (pin "2") (pinfunction "2_2") (pintype "passive"))
      (node (ref "C23") (pin "2") (pinfunction "2_2") (pintype "passive"))
      (node (ref "C24") (pin "2") (pinfunction "2_2") (pintype "passive"))
      (node (ref "C25") (pin "2") (pinfunction "2_2") (pintype "passive"))
      (node (ref "C26") (pin "2") (pinfunction "2_2") (pintype "passive"))
      (node (ref "C27") (pin "2") (pinfunction "2_2") (pintype "passive"))
      (node (ref "C28") (pin "2") (pinfunction "2_2") (pintype "passive"))
      (node (ref "C29") (pin "1") (pinfunction "1_1") (pintype "passive"))
      (node (ref "C3") (pin "2") (pinfunction "2_2") (pintype "passive"))
      (node (ref "C30") (pin "1") (pinfunction "1_1") (pintype "passive"))
      (node (ref "C31") (pin "1") (pinfunction "1_1") (pintype "passive"))
      (node (ref "C32") (pin "2") (pinfunction "2_2") (pintype "passive"))
      (node (ref "C33") (pin "2") (pinfunction "2_2") (pintype "passive"))
      (node (ref "C34") (pin "2") (pinfunction "2_2") (pintype "passive"))
      (node (ref "C35") (pin "2") (pinfunction "2_2") (pintype "passive"))
      (node (ref "C36") (pin "2") (pinfunction "2_2") (pintype "passive"))
      (node (ref "C37") (pin "2") (pinfunction "2_2") (pintype "passive"))
      (node (ref "C38") (pin "2") (pinfunction "2_2") (pintype "passive"))
      (node (ref "C39") (pin "2") (pinfunction "2_2") (pintype "passive"))
      (node (ref "C4") (pin "1") (pinfunction "1_1") (pintype "passive"))
      (node (ref "C40") (pin "2") (pinfunction "2_2") (pintype "passive"))
      (node (ref "C41") (pin "2") (pinfunction "2_2") (pintype "passive"))
      (node (ref "C5") (pin "2") (pinfunction "2_2") (pintype "passive"))
      (node (ref "C6") (pin "2") (pinfunction "2_2") (pintype "passive"))
      (node (ref "C7") (pin "1") (pinfunction "1_1") (pintype "passive"))
      (node (ref "C8") (pin "2") (pinfunction "2_2") (pintype "passive"))
      (node (ref "C9") (pin "2") (pinfunction "2_2") (pintype "passive"))
      (node (ref "D1") (pin "2") (pinfunction "K_2") (pintype "passive"))
      (node (ref "D2") (pin "2") (pinfunction "K_2") (pintype "passive"))
      (node (ref "IC1") (pin "104") (pinfunction "VSS_10_104") (pintype "passive"))
      (node (ref "IC1") (pin "118") (pinfunction "VSS_11_118") (pintype "passive"))
      (node (ref "IC1") (pin "12") (pinfunction "VSS_2_12") (pintype "passive"))
      (node (ref "IC1") (pin "128") (pinfunction "VSS_12_128") (pintype "passive"))
      (node (ref "IC1") (pin "14") (pinfunction "VSSSMPS_14") (pintype "passive"))
      (node (ref "IC1") (pin "141") (pinfunction "VSS_13_141") (pintype "passive"))
      (node (ref "IC1") (pin "15") (pinfunction "VLXSMPS_15") (pintype "passive"))
      (node (ref "IC1") (pin "16") (pinfunction "VDDSMPS_16") (pintype "passive"))
      (node (ref "IC1") (pin "17") (pinfunction "VFBSMPS_17") (pintype "passive"))
      (node (ref "IC1") (pin "18") (pinfunction "VSS_3_18") (pintype "passive"))
      (node (ref "IC1") (pin "33") (pinfunction "VSS_4_33") (pintype "passive"))
      (node (ref "IC1") (pin "34") (pinfunction "VSSA_34") (pintype "passive"))
      (node (ref "IC1") (pin "41") (pinfunction "VSS_5_41") (pintype "passive"))
      (node (ref "IC1") (pin "55") (pinfunction "VSS_6_55") (pintype "passive"))
      (node (ref "IC1") (pin "6") (pinfunction "VSS_1_6") (pintype "passive"))
      (node (ref "IC1") (pin "69") (pinfunction "VSS_7_69") (pintype "passive"))
      (node (ref "IC1") (pin "80") (pinfunction "VSS_8_80") (pintype "passive"))
      (node (ref "IC1") (pin "89") (pinfunction "VSS_9_89") (pintype "passive"))
      (node (ref "IC2") (pin "1") (pinfunction "GND_1_1") (pintype "passive"))
      (node (ref "IC2") (pin "2") (pinfunction "GND_2_2") (pintype "passive"))
      (node (ref "IC2") (pin "33") (pinfunction "GND_3_33") (pintype "passive"))
      (node (ref "IC3") (pin "B1") (pinfunction "CK#_B1") (pintype "passive"))
      (node (ref "IC3") (pin "B3") (pinfunction "VSS_B3") (pintype "passive"))
      (node (ref "IC3") (pin "C1") (pinfunction "VSSQ_1_C1") (pintype "passive"))
      (node (ref "IC3") (pin "E5") (pinfunction "VSSQ_2_E5") (pintype "passive"))
      (node (ref "J1") (pin "10") (pinfunction "10_10") (pintype "passive"))
      (node (ref "J1") (pin "11") (pinfunction "11_11") (pintype "passive"))
      (node (ref "J1") (pin "12") (pinfunction "12_12") (pintype "passive"))
      (node (ref "J1") (pin "6") (pinfunction "6_6") (pintype "passive"))
      (node (ref "J1") (pin "9") (pinfunction "9_9") (pintype "passive"))
      (node (ref "J2") (pin "3") (pinfunction "3_3") (pintype "passive"))
      (node (ref "J3") (pin "3") (pinfunction "3_3") (pintype "passive"))
      (node (ref "Q1") (pin "2") (pintype "passive"))
      (node (ref "Q1") (pin "4") (pintype "passive"))
      (node (ref "Q3") (pin "P$2") (pinfunction "2_P$2") (pintype "passive"))
      (node (ref "Q3") (pin "P$4") (pinfunction "4_P$4") (pintype "passive"))
      (node (ref "R12") (pin "1") (pinfunction "1_1") (pintype "passive"))
      (node (ref "R13") (pin "1") (pinfunction "1_1") (pintype "passive"))
      (node (ref "R14") (pin "1") (pinfunction "1_1") (pintype "passive"))
      (node (ref "R15") (pin "1") (pinfunction "1_1") (pintype "passive"))
      (node (ref "R33") (pin "1") (pinfunction "1_1") (pintype "passive"))
      (node (ref "R34") (pin "1") (pinfunction "1_1") (pintype "passive"))
      (node (ref "R6") (pin "1") (pinfunction "1_1") (pintype "passive"))
      (node (ref "R7") (pin "1") (pinfunction "1_1") (pintype "passive"))
      (node (ref "R8") (pin "1") (pinfunction "1_1") (pintype "passive"))
      (node (ref "R9") (pin "1") (pinfunction "1_1") (pintype "passive"))
      (node (ref "S1") (pin "1") (pinfunction "S_1") (pintype "passive"))
      (node (ref "S1") (pin "2") (pinfunction "S1_2") (pintype "passive"))
      (node (ref "SV1") (pin "5") (pinfunction "5_5") (pintype "passive"))
      (node (ref "SV1") (pin "6") (pinfunction "6_6") (pintype "passive"))
      (node (ref "U1") (pin "2") (pinfunction "GND1_2") (pintype "power_in"))
      (node (ref "U1") (pin "3") (pinfunction "GND2_3") (pintype "power_in"))
      (node (ref "U1") (pin "5") (pinfunction "INHIBIT_5") (pintype "passive"))
      (node (ref "U1") (pin "6") (pinfunction "GND3_6") (pintype "power_in"))
      (node (ref "U1") (pin "7") (pinfunction "GND4_7") (pintype "power_in"))
      (node (ref "U2") (pin "2") (pinfunction "GND_2") (pintype "passive"))
      (node (ref "U3") (pin "2") (pinfunction "GND_2") (pintype "passive"))
      (node (ref "USB1") (pin "GND") (pinfunction "GND_GND") (pintype "passive"))
      (node (ref "X1") (pin "10") (pinfunction "KL_10") (pintype "passive"))
      (node (ref "X1") (pin "12") (pinfunction "KL_12") (pintype "passive"))
      (node (ref "X1") (pin "14") (pinfunction "KL_14") (pintype "passive"))
      (node (ref "X1") (pin "16") (pinfunction "KL_16") (pintype "passive"))
      (node (ref "X1") (pin "18") (pinfunction "KL_18") (pintype "passive"))
      (node (ref "X1") (pin "20") (pinfunction "KL_20") (pintype "passive"))
      (node (ref "X1") (pin "4") (pinfunction "KL_4") (pintype "passive"))
      (node (ref "X1") (pin "6") (pinfunction "KL_6") (pintype "passive"))
      (node (ref "X1") (pin "8") (pinfunction "KL_8") (pintype "passive"))
    )
    (net (code "58") (name "Net-(C5-Pad1)") (class "Default")
      (node (ref "C5") (pin "1") (pinfunction "1_1") (pintype "passive"))
      (node (ref "R9") (pin "2") (pinfunction "2_2") (pintype "passive"))
      (node (ref "USB1") (pin "PAD1") (pinfunction "PAD1_PAD1") (pintype "passive"))
      (node (ref "USB1") (pin "PAD2") (pinfunction "PAD2_PAD2") (pintype "passive"))
      (node (ref "USB1") (pin "PAD3") (pinfunction "PAD3_PAD3") (pintype "passive"))
      (node (ref "USB1") (pin "PAD4") (pinfunction "PAD4_PAD4") (pintype "passive"))
      (node (ref "USB1") (pin "PAD5") (pinfunction "PAD5_PAD5") (pintype "passive"))
      (node (ref "USB1") (pin "PAD6") (pinfunction "PAD6_PAD6") (pintype "passive"))
    )
    (net (code "59") (name "Net-(C38-Pad1)") (class "Default")
      (node (ref "C38") (pin "1") (pinfunction "1_1") (pintype "passive"))
      (node (ref "R27") (pin "1") (pinfunction "1_1") (pintype "passive"))
      (node (ref "R35") (pin "2") (pinfunction "2_2") (pintype "passive"))
    )
    (net (code "60") (name "Net-(C39-Pad1)") (class "Default")
      (node (ref "C39") (pin "1") (pinfunction "1_1") (pintype "passive"))
      (node (ref "R28") (pin "1") (pinfunction "1_1") (pintype "passive"))
      (node (ref "R36") (pin "2") (pinfunction "2_2") (pintype "passive"))
    )
    (net (code "61") (name "Net-(D1-A)") (class "Default")
      (node (ref "D1") (pin "1") (pinfunction "A_1") (pintype "passive"))
      (node (ref "R16") (pin "2") (pinfunction "2_2") (pintype "passive"))
    )
    (net (code "62") (name "Net-(D2-A)") (class "Default")
      (node (ref "D2") (pin "1") (pinfunction "A_1") (pintype "passive"))
      (node (ref "R18") (pin "2") (pinfunction "2_2") (pintype "passive"))
    )
    (net (code "63") (name "Net-(D3-A)") (class "Default")
      (node (ref "C40") (pin "1") (pinfunction "1_1") (pintype "passive"))
      (node (ref "D3") (pin "3") (pinfunction "A_3") (pintype "passive"))
      (node (ref "R33") (pin "2") (pinfunction "2_2") (pintype "passive"))
    )
    (net (code "64") (name "Net-(D3-K1)") (class "Default")
      (node (ref "D3") (pin "1") (pinfunction "K1_1") (pintype "passive"))
      (node (ref "R27") (pin "2") (pinfunction "2_2") (pintype "passive"))
      (node (ref "R29") (pin "1") (pinfunction "1_1") (pintype "passive"))
      (node (ref "U2") (pin "6") (pinfunction "CAN_L_6") (pintype "passive"))
    )
    (net (code "65") (name "Net-(D3-K2)") (class "Default")
      (node (ref "D3") (pin "2") (pinfunction "K2_2") (pintype "passive"))
      (node (ref "R31") (pin "1") (pinfunction "1_1") (pintype "passive"))
      (node (ref "R35") (pin "1") (pinfunction "1_1") (pintype "passive"))
      (node (ref "U2") (pin "7") (pinfunction "CAN_H_7") (pintype "passive"))
    )
    (net (code "66") (name "Net-(D4-A)") (class "Default")
      (node (ref "C41") (pin "1") (pinfunction "1_1") (pintype "passive"))
      (node (ref "D4") (pin "3") (pinfunction "A_3") (pintype "passive"))
      (node (ref "R34") (pin "2") (pinfunction "2_2") (pintype "passive"))
    )
    (net (code "67") (name "Net-(D4-K1)") (class "Default")
      (node (ref "D4") (pin "1") (pinfunction "K1_1") (pintype "passive"))
      (node (ref "R28") (pin "2") (pinfunction "2_2") (pintype "passive"))
      (node (ref "R30") (pin "1") (pinfunction "1_1") (pintype "passive"))
      (node (ref "U3") (pin "6") (pinfunction "CAN_L_6") (pintype "passive"))
    )
    (net (code "68") (name "Net-(D4-K2)") (class "Default")
      (node (ref "D4") (pin "2") (pinfunction "K2_2") (pintype "passive"))
      (node (ref "R32") (pin "1") (pinfunction "1_1") (pintype "passive"))
      (node (ref "R36") (pin "1") (pinfunction "1_1") (pintype "passive"))
      (node (ref "U3") (pin "7") (pinfunction "CAN_H_7") (pintype "passive"))
    )
    (net (code "69") (name "Net-(IC1-BOOT0)") (class "Default")
      (node (ref "IC1") (pin "135") (pinfunction "BOOT0_135") (pintype "passive"))
      (node (ref "R6") (pin "2") (pinfunction "2_2") (pintype "passive"))
    )
    (net (code "70") (name "Net-(IC1-PC14-OSC32_IN)") (class "Default")
      (node (ref "C16") (pin "2") (pinfunction "2_2") (pintype "passive"))
      (node (ref "IC1") (pin "10") (pinfunction "PC14-OSC32_IN_10") (pintype "passive"))
      (node (ref "Q2") (pin "2") (pinfunction "2_2") (pintype "passive"))
    )
    (net (code "71") (name "Net-(IC1-PC15-OSC32_OUT)") (class "Default")
      (node (ref "C17") (pin "2") (pinfunction "2_2") (pintype "passive"))
      (node (ref "IC1") (pin "11") (pinfunction "PC15-OSC32_OUT_11") (pintype "passive"))
      (node (ref "Q2") (pin "1") (pinfunction "1_1") (pintype "passive"))
    )
    (net (code "72") (name "Net-(IC1-PH0-OSC_IN)") (class "Default")
      (node (ref "C26") (pin "1") (pinfunction "1_1") (pintype "passive"))
      (node (ref "IC1") (pin "25") (pinfunction "PH0-OSC_IN_25") (pintype "passive"))
      (node (ref "Q3") (pin "P$1") (pinfunction "1_P$1") (pintype "passive"))
      (node (ref "R17") (pin "2") (pinfunction "2_2") (pintype "passive"))
    )
    (net (code "73") (name "Net-(IC1-PH1-OSC_OUT)") (class "Default")
      (node (ref "C27") (pin "1") (pinfunction "1_1") (pintype "passive"))
      (node (ref "IC1") (pin "26") (pinfunction "PH1-OSC_OUT_26") (pintype "passive"))
      (node (ref "Q3") (pin "P$3") (pinfunction "3_P$3") (pintype "passive"))
      (node (ref "R17") (pin "1") (pinfunction "1_1") (pintype "passive"))
    )
    (net (code "74") (name "Net-(IC1-VCAP_1)") (class "Default")
      (node (ref "C34") (pin "1") (pinfunction "1_1") (pintype "passive"))
      (node (ref "IC1") (pin "68") (pinfunction "VCAP_1_68") (pintype "passive"))
    )
    (net (code "75") (name "Net-(IC2-RBIAS)") (class "Default")
      (node (ref "IC2") (pin "32") (pinfunction "RBIAS_32") (pintype "passive"))
      (node (ref "R14") (pin "2") (pinfunction "2_2") (pintype "passive"))
    )
    (net (code "76") (name "Net-(IC2-RESET)") (class "Default")
      (node (ref "IC2") (pin "9") (pinfunction "RESET_9") (pintype "passive"))
      (node (ref "R15") (pin "2") (pinfunction "2_2") (pintype "passive"))
    )
    (net (code "77") (name "Net-(IC2-VBUS)") (class "Default")
      (node (ref "IC2") (pin "4") (pinfunction "VBUS_4") (pintype "passive"))
      (node (ref "R50") (pin "2") (pinfunction "2_2") (pintype "passive"))
    )
    (net (code "78") (name "Net-(IC2-VDD1.8_2)") (class "Default")
      (node (ref "C9") (pin "1") (pinfunction "1_1") (pintype "passive"))
      (node (ref "IC2") (pin "26") (pinfunction "VDD1.8_2_26") (pintype "passive"))
    )
    (net (code "79") (name "Net-(IC2-VDDA1.8)") (class "Default")
      (node (ref "C6") (pin "1") (pinfunction "1_1") (pintype "passive"))
      (node (ref "IC2") (pin "29") (pinfunction "VDDA1.8_29") (pintype "passive"))
    )
    (net (code "80") (name "Net-(IC2-XI)") (class "Default")
      (node (ref "C4") (pin "2") (pinfunction "2_2") (pintype "passive"))
      (node (ref "IC2") (pin "28") (pinfunction "XI_28") (pintype "passive"))
      (node (ref "Q1") (pin "3") (pintype "power_in"))
    )
    (net (code "81") (name "Net-(IC2-XO)") (class "Default")
      (node (ref "C7") (pin "2") (pinfunction "2_2") (pintype "passive"))
      (node (ref "IC2") (pin "27") (pinfunction "XO_27") (pintype "passive"))
      (node (ref "Q1") (pin "1") (pintype "power_in"))
    )
    (net (code "82") (name "Net-(L1-Pad1)") (class "Default")
      (node (ref "L1") (pin "1") (pinfunction "1_1") (pintype "passive"))
      (node (ref "USB1") (pin "V") (pinfunction "V_V") (pintype "passive"))
    )
    (net (code "83") (name "Net-(R1-Pad1)") (class "Default")
      (node (ref "R1") (pin "1") (pinfunction "1_1") (pintype "passive"))
      (node (ref "USB1") (pin "D-") (pinfunction "D-_D-") (pintype "passive"))
    )
    (net (code "84") (name "Net-(R3-Pad1)") (class "Default")
      (node (ref "R3") (pin "1") (pinfunction "1_1") (pintype "passive"))
      (node (ref "USB1") (pin "D+") (pinfunction "D+_D+") (pintype "passive"))
    )
    (net (code "85") (name "Net-(X1K-KL)") (class "Default")
      (node (ref "R8") (pin "2") (pinfunction "2_2") (pintype "passive"))
      (node (ref "X1") (pin "11") (pinfunction "KL_11") (pintype "passive"))
    )
    (net (code "86") (name "Net-(X1Q-KL)") (class "Default")
      (node (ref "R12") (pin "2") (pinfunction "2_2") (pintype "passive"))
      (node (ref "X1") (pin "17") (pinfunction "KL_17") (pintype "passive"))
    )
    (net (code "87") (name "Net-(X1S-KL)") (class "Default")
      (node (ref "R13") (pin "2") (pinfunction "2_2") (pintype "passive"))
      (node (ref "X1") (pin "19") (pinfunction "KL_19") (pintype "passive"))
    )
    (net (code "88") (name "unconnected-(IC1-PA0-Pad37)") (class "Default")
      (node (ref "IC1") (pin "37") (pinfunction "PA0_37") (pintype "passive"))
    )
    (net (code "89") (name "unconnected-(IC1-PA4-Pad43)") (class "Default")
      (node (ref "IC1") (pin "43") (pinfunction "PA4_43") (pintype "passive"))
    )
    (net (code "90") (name "unconnected-(IC1-PA6-Pad45)") (class "Default")
      (node (ref "IC1") (pin "45") (pinfunction "PA6_45") (pintype "passive"))
    )
    (net (code "91") (name "unconnected-(IC1-PA7-Pad46)") (class "Default")
      (node (ref "IC1") (pin "46") (pinfunction "PA7_46") (pintype "passive"))
    )
    (net (code "92") (name "unconnected-(IC1-PA8-Pad97)") (class "Default")
      (node (ref "IC1") (pin "97") (pinfunction "PA8_97") (pintype "passive"))
    )
    (net (code "93") (name "unconnected-(IC1-PA9-Pad98)") (class "Default")
      (node (ref "IC1") (pin "98") (pinfunction "PA9_98") (pintype "passive"))
    )
    (net (code "94") (name "unconnected-(IC1-PB2-Pad51)") (class "Default")
      (node (ref "IC1") (pin "51") (pinfunction "PB2_51") (pintype "passive"))
    )
    (net (code "95") (name "unconnected-(IC1-PB6-Pad133)") (class "Default")
      (node (ref "IC1") (pin "133") (pinfunction "PB6_133") (pintype "passive"))
    )
    (net (code "96") (name "unconnected-(IC1-PB7-Pad134)") (class "Default")
      (node (ref "IC1") (pin "134") (pinfunction "PB7_134") (pintype "passive"))
    )
    (net (code "97") (name "unconnected-(IC1-PB8-Pad136)") (class "Default")
      (node (ref "IC1") (pin "136") (pinfunction "PB8_136") (pintype "passive"))
    )
    (net (code "98") (name "unconnected-(IC1-PB9-Pad137)") (class "Default")
      (node (ref "IC1") (pin "137") (pinfunction "PB9_137") (pintype "passive"))
    )
    (net (code "99") (name "unconnected-(IC1-PC4-Pad47)") (class "Default")
      (node (ref "IC1") (pin "47") (pinfunction "PC4_47") (pintype "passive"))
    )
    (net (code "100") (name "unconnected-(IC1-PC6-Pad93)") (class "Default")
      (node (ref "IC1") (pin "93") (pinfunction "PC6_93") (pintype "passive"))
    )
    (net (code "101") (name "unconnected-(IC1-PC7-Pad94)") (class "Default")
      (node (ref "IC1") (pin "94") (pinfunction "PC7_94") (pintype "passive"))
    )
    (net (code "102") (name "unconnected-(IC1-PC13-Pad9)") (class "Default")
      (node (ref "IC1") (pin "9") (pinfunction "PC13_9") (pintype "passive"))
    )
    (net (code "103") (name "unconnected-(IC1-PD0-Pad112)") (class "Default")
      (node (ref "IC1") (pin "112") (pinfunction "PD0_112") (pintype "passive"))
    )
    (net (code "104") (name "unconnected-(IC1-PD1-Pad113)") (class "Default")
      (node (ref "IC1") (pin "113") (pinfunction "PD1_113") (pintype "passive"))
    )
    (net (code "105") (name "unconnected-(IC1-PD3-Pad115)") (class "Default")
      (node (ref "IC1") (pin "115") (pinfunction "PD3_115") (pintype "passive"))
    )
    (net (code "106") (name "unconnected-(IC1-PD4-Pad116)") (class "Default")
      (node (ref "IC1") (pin "116") (pinfunction "PD4_116") (pintype "passive"))
    )
    (net (code "107") (name "unconnected-(IC1-PD5-Pad117)") (class "Default")
      (node (ref "IC1") (pin "117") (pinfunction "PD5_117") (pintype "passive"))
    )
    (net (code "108") (name "unconnected-(IC1-PD6-Pad120)") (class "Default")
      (node (ref "IC1") (pin "120") (pinfunction "PD6_120") (pintype "passive"))
    )
    (net (code "109") (name "unconnected-(IC1-PD7-Pad121)") (class "Default")
      (node (ref "IC1") (pin "121") (pinfunction "PD7_121") (pintype "passive"))
    )
    (net (code "110") (name "unconnected-(IC1-PD8-Pad76)") (class "Default")
      (node (ref "IC1") (pin "76") (pinfunction "PD8_76") (pintype "passive"))
    )
    (net (code "111") (name "unconnected-(IC1-PD9-Pad77)") (class "Default")
      (node (ref "IC1") (pin "77") (pinfunction "PD9_77") (pintype "passive"))
    )
    (net (code "112") (name "unconnected-(IC1-PD10-Pad78)") (class "Default")
      (node (ref "IC1") (pin "78") (pinfunction "PD10_78") (pintype "passive"))
    )
    (net (code "113") (name "unconnected-(IC1-PD11-Pad81)") (class "Default")
      (node (ref "IC1") (pin "81") (pinfunction "PD11_81") (pintype "passive"))
    )
    (net (code "114") (name "unconnected-(IC1-PD12-Pad82)") (class "Default")
      (node (ref "IC1") (pin "82") (pinfunction "PD12_82") (pintype "passive"))
    )
    (net (code "115") (name "unconnected-(IC1-PD13-Pad83)") (class "Default")
      (node (ref "IC1") (pin "83") (pinfunction "PD13_83") (pintype "passive"))
    )
    (net (code "116") (name "unconnected-(IC1-PD14-Pad84)") (class "Default")
      (node (ref "IC1") (pin "84") (pinfunction "PD14_84") (pintype "passive"))
    )
    (net (code "117") (name "unconnected-(IC1-PD15-Pad85)") (class "Default")
      (node (ref "IC1") (pin "85") (pinfunction "PD15_85") (pintype "passive"))
    )
    (net (code "118") (name "unconnected-(IC1-PDR_ON-Pad142)") (class "Default")
      (node (ref "IC1") (pin "142") (pinfunction "PDR_ON_142") (pintype "passive"))
    )
    (net (code "119") (name "unconnected-(IC1-PE0-Pad138)") (class "Default")
      (node (ref "IC1") (pin "138") (pinfunction "PE0_138") (pintype "passive"))
    )
    (net (code "120") (name "unconnected-(IC1-PE1-Pad139)") (class "Default")
      (node (ref "IC1") (pin "139") (pinfunction "PE1_139") (pintype "passive"))
    )
    (net (code "121") (name "unconnected-(IC1-PE5-Pad4)") (class "Default")
      (node (ref "IC1") (pin "4") (pinfunction "PE5_4") (pintype "passive"))
    )
    (net (code "122") (name "unconnected-(IC1-PE6-Pad5)") (class "Default")
      (node (ref "IC1") (pin "5") (pinfunction "PE6_5") (pintype "passive"))
    )
    (net (code "123") (name "unconnected-(IC1-PE7-Pad57)") (class "Default")
      (node (ref "IC1") (pin "57") (pinfunction "PE7_57") (pintype "passive"))
    )
    (net (code "124") (name "unconnected-(IC1-PE12-Pad62)") (class "Default")
      (node (ref "IC1") (pin "62") (pinfunction "PE12_62") (pintype "passive"))
    )
    (net (code "125") (name "unconnected-(IC1-PE13-Pad63)") (class "Default")
      (node (ref "IC1") (pin "63") (pinfunction "PE13_63") (pintype "passive"))
    )
    (net (code "126") (name "unconnected-(IC1-PE14-Pad64)") (class "Default")
      (node (ref "IC1") (pin "64") (pinfunction "PE14_64") (pintype "passive"))
    )
    (net (code "127") (name "unconnected-(IC1-PE15-Pad65)") (class "Default")
      (node (ref "IC1") (pin "65") (pinfunction "PE15_65") (pintype "passive"))
    )
    (net (code "128") (name "unconnected-(IC1-PF11-Pad52)") (class "Default")
      (node (ref "IC1") (pin "52") (pinfunction "PF11_52") (pintype "passive"))
    )
    (net (code "129") (name "unconnected-(IC1-PF14-Pad53)") (class "Default")
      (node (ref "IC1") (pin "53") (pinfunction "PF14_53") (pintype "passive"))
    )
    (net (code "130") (name "unconnected-(IC1-PF15-Pad54)") (class "Default")
      (node (ref "IC1") (pin "54") (pinfunction "PF15_54") (pintype "passive"))
    )
    (net (code "131") (name "unconnected-(IC1-PG6-Pad86)") (class "Default")
      (node (ref "IC1") (pin "86") (pinfunction "PG6_86") (pintype "passive"))
    )
    (net (code "132") (name "unconnected-(IC1-PG7-Pad87)") (class "Default")
      (node (ref "IC1") (pin "87") (pinfunction "PG7_87") (pintype "passive"))
    )
    (net (code "133") (name "unconnected-(IC1-PG8-Pad88)") (class "Default")
      (node (ref "IC1") (pin "88") (pinfunction "PG8_88") (pintype "passive"))
    )
    (net (code "134") (name "unconnected-(IC1-PG9-Pad122)") (class "Default")
      (node (ref "IC1") (pin "122") (pinfunction "PG9_122") (pintype "passive"))
    )
    (net (code "135") (name "unconnected-(IC1-PG10-Pad123)") (class "Default")
      (node (ref "IC1") (pin "123") (pinfunction "PG10_123") (pintype "passive"))
    )
    (net (code "136") (name "unconnected-(IC1-PG11-Pad124)") (class "Default")
      (node (ref "IC1") (pin "124") (pinfunction "PG11_124") (pintype "passive"))
    )
    (net (code "137") (name "unconnected-(IC1-PG12-Pad125)") (class "Default")
      (node (ref "IC1") (pin "125") (pinfunction "PG12_125") (pintype "passive"))
    )
    (net (code "138") (name "unconnected-(IC1-PG13-Pad126)") (class "Default")
      (node (ref "IC1") (pin "126") (pinfunction "PG13_126") (pintype "passive"))
    )
    (net (code "139") (name "unconnected-(IC1-PG14-Pad127)") (class "Default")
      (node (ref "IC1") (pin "127") (pinfunction "PG14_127") (pintype "passive"))
    )
    (net (code "140") (name "unconnected-(IC1-VDD33USB-Pad91)") (class "Default")
      (node (ref "IC1") (pin "91") (pinfunction "VDD33USB_91") (pintype "passive"))
    )
    (net (code "141") (name "unconnected-(IC1-VDD50USB-Pad90)") (class "Default")
      (node (ref "IC1") (pin "90") (pinfunction "VDD50USB_90") (pintype "passive"))
    )
    (net (code "142") (name "unconnected-(IC2-CPEN-Pad3)") (class "Default")
      (node (ref "IC2") (pin "3") (pinfunction "CPEN_3") (pintype "passive"))
    )
    (net (code "143") (name "unconnected-(IC2-EXTVBUS-Pad10)") (class "Default")
      (node (ref "IC2") (pin "10") (pinfunction "EXTVBUS_10") (pintype "passive"))
    )
    (net (code "144") (name "unconnected-(IC3-RFU_1-PadA2)") (class "Default")
      (node (ref "IC3") (pin "A2") (pinfunction "RFU_1_A2") (pintype "passive"))
    )
    (net (code "145") (name "unconnected-(IC3-RFU_2-PadA5)") (class "Default")
      (node (ref "IC3") (pin "A5") (pinfunction "RFU_2_A5") (pintype "passive+no_connect"))
    )
    (net (code "146") (name "unconnected-(IC3-RFU_3-PadB5)") (class "Default")
      (node (ref "IC3") (pin "B5") (pinfunction "RFU_3_B5") (pintype "passive+no_connect"))
    )
    (net (code "147") (name "unconnected-(IC3-RFU_4-PadC2)") (class "Default")
      (node (ref "IC3") (pin "C2") (pinfunction "RFU_4_C2") (pintype "passive+no_connect"))
    )
    (net (code "148") (name "unconnected-(IC3-RFU_5-PadC5)") (class "Default")
      (node (ref "IC3") (pin "C5") (pinfunction "RFU_5_C5") (pintype "passive"))
    )
    (net (code "149") (name "unconnected-(J2-MH1-Pad10)") (class "Default")
      (node (ref "J2") (pin "10") (pinfunction "MH1_10") (pintype "passive"))
    )
    (net (code "150") (name "unconnected-(J2-MH2-Pad11)") (class "Default")
      (node (ref "J2") (pin "11") (pinfunction "MH2_11") (pintype "passive"))
    )
    (net (code "151") (name "unconnected-(J2-Pad1)") (class "Default")
      (node (ref "J2") (pin "1") (pinfunction "1_1") (pintype "passive"))
    )
    (net (code "152") (name "unconnected-(J2-Pad4)") (class "Default")
      (node (ref "J2") (pin "4") (pinfunction "4_4") (pintype "passive"))
    )
    (net (code "153") (name "unconnected-(J2-Pad5)") (class "Default")
      (node (ref "J2") (pin "5") (pinfunction "5_5") (pintype "passive"))
    )
    (net (code "154") (name "unconnected-(J2-Pad6)") (class "Default")
      (node (ref "J2") (pin "6") (pinfunction "6_6") (pintype "passive"))
    )
    (net (code "155") (name "unconnected-(J2-Pad8)") (class "Default")
      (node (ref "J2") (pin "8") (pinfunction "8_8") (pintype "passive"))
    )
    (net (code "156") (name "unconnected-(J2-Pad9)") (class "Default")
      (node (ref "J2") (pin "9") (pinfunction "9_9") (pintype "passive"))
    )
    (net (code "157") (name "unconnected-(J3-MH1-Pad10)") (class "Default")
      (node (ref "J3") (pin "10") (pinfunction "MH1_10") (pintype "passive"))
    )
    (net (code "158") (name "unconnected-(J3-MH2-Pad11)") (class "Default")
      (node (ref "J3") (pin "11") (pinfunction "MH2_11") (pintype "passive"))
    )
    (net (code "159") (name "unconnected-(J3-Pad1)") (class "Default")
      (node (ref "J3") (pin "1") (pinfunction "1_1") (pintype "passive"))
    )
    (net (code "160") (name "unconnected-(J3-Pad4)") (class "Default")
      (node (ref "J3") (pin "4") (pinfunction "4_4") (pintype "passive"))
    )
    (net (code "161") (name "unconnected-(J3-Pad5)") (class "Default")
      (node (ref "J3") (pin "5") (pinfunction "5_5") (pintype "passive"))
    )
    (net (code "162") (name "unconnected-(J3-Pad6)") (class "Default")
      (node (ref "J3") (pin "6") (pinfunction "6_6") (pintype "passive"))
    )
    (net (code "163") (name "unconnected-(J3-Pad8)") (class "Default")
      (node (ref "J3") (pin "8") (pinfunction "8_8") (pintype "passive"))
    )
    (net (code "164") (name "unconnected-(J3-Pad9)") (class "Default")
      (node (ref "J3") (pin "9") (pinfunction "9_9") (pintype "passive"))
    )
    (net (code "165") (name "unconnected-(U1-NC-Pad4)") (class "Default")
      (node (ref "U1") (pin "4") (pinfunction "NC_4") (pintype "passive"))
    )
  )
)
